# Boost.net
KiCad netlist of a schematic drawn in Altium Designer
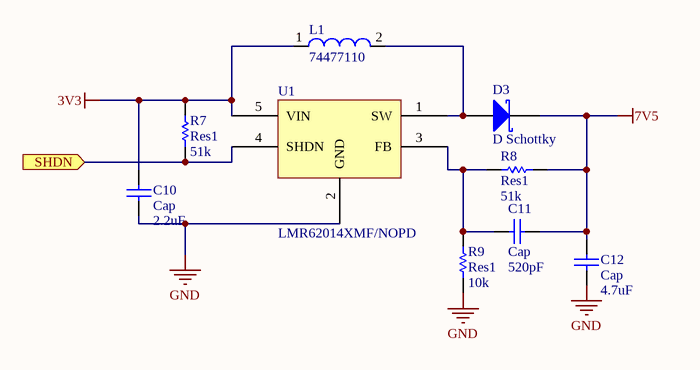
[diagram p0: Boost.SchDoc]

(export (version "E")
  (design (tool "Eeschema 10.0.6"))
  (components
    (comp (ref "C10")
      (value "Cap")
      (footprint "1608[0603]")
      (description "Capacitor")
      (fields (field (name "ALTIUM_VALUE") "2.2uF") (field (name "PUBLISHER") "Altium Limited"))
      (libsource (lib "Miscellaneous Devices") (part "Cap"))
    )
    (comp (ref "C11")
      (value "Cap")
      (footprint "6-0805_N")
      (description "Capacitor")
      (fields (field (name "ALTIUM_VALUE") "520pF") (field (name "PUBLISHER") "Altium Limited"))
      (libsource (lib "Miscellaneous Devices") (part "Cap"))
    )
    (comp (ref "C12")
      (value "Cap")
      (footprint "6-0805_N")
      (description "Capacitor")
      (fields (field (name "ALTIUM_VALUE") "4.7uF") (field (name "PUBLISHER") "Altium Limited"))
      (libsource (lib "Miscellaneous Devices") (part "Cap"))
    )
    (comp (ref "D3")
      (value "D Schottky")
      (footprint "CDBA5")
      (description "Schottky Diode")
      (fields (field (name "PUBLISHER") "Altium Limited"))
      (libsource (lib "Miscellaneous Devices") (part "D Schottky"))
    )
    (comp (ref "L1")
      (value "74477110")
      (footprint "WE-PD-L")
      (description "SMD-Shielded Power Inductor WE-PD, L = 10.0 µH")
      (libsource (lib "Altium Content Vault") (part "PAS-IND-INDUCTOR-2"))
    )
    (comp (ref "R7")
      (value "Res1")
      (footprint "1608[0603]")
      (description "Resistor")
      (fields (field (name "ALTIUM_VALUE") "51k") (field (name "PUBLISHER") "Altium Limited"))
      (libsource (lib "Miscellaneous Devices") (part "Res1"))
    )
    (comp (ref "R8")
      (value "Res1")
      (footprint "1608[0603]")
      (description "Resistor")
      (fields (field (name "ALTIUM_VALUE") "51k") (field (name "PUBLISHER") "Altium Limited"))
      (libsource (lib "Miscellaneous Devices") (part "Res1"))
    )
    (comp (ref "R9")
      (value "Res1")
      (footprint "0402-A")
      (description "Resistor")
      (fields (field (name "ALTIUM_VALUE") "10k") (field (name "PUBLISHER") "Altium Limited"))
      (libsource (lib "Miscellaneous Devices") (part "Res1"))
    )
    (comp (ref "U1")
      (value "LMR62014XMF/NOPD")
      (footprint "SOT95P280X145-5N")
      (libsource (lib "BPDC Library") (part "LMR62014XMF/NOPD"))
    )
  )
  (nets
    (net (code "1") (name "/SHDN") (class "Default")
      (node (ref "R7") (pin "2") (pinfunction "2_2") (pintype "passive"))
      (node (ref "U1") (pin "4") (pinfunction "SHDN_4") (pintype "passive"))
    )
    (net (code "2") (name "3V3") (class "Default")
      (node (ref "C10") (pin "2") (pinfunction "2_2") (pintype "passive"))
      (node (ref "L1") (pin "1") (pinfunction "1_1") (pintype "passive"))
      (node (ref "R7") (pin "1") (pinfunction "1_1") (pintype "passive"))
      (node (ref "U1") (pin "5") (pinfunction "VIN_5") (pintype "passive"))
    )
    (net (code "3") (name "7V5") (class "Default")
      (node (ref "C11") (pin "1") (pinfunction "1_1") (pintype "passive"))
      (node (ref "C12") (pin "2") (pinfunction "2_2") (pintype "passive"))
      (node (ref "D3") (pin "2") (pinfunction "K_2") (pintype "passive"))
      (node (ref "R8") (pin "2") (pinfunction "2_2") (pintype "passive"))
    )
    (net (code "4") (name "GND") (class "Default")
      (node (ref "C10") (pin "1") (pinfunction "1_1") (pintype "passive"))
      (node (ref "C12") (pin "1") (pinfunction "1_1") (pintype "passive"))
      (node (ref "R9") (pin "2") (pinfunction "2_2") (pintype "passive"))
      (node (ref "U1") (pin "2") (pinfunction "GND_2") (pintype "passive"))
    )
    (net (code "5") (name "Net-(D3-A)") (class "Default")
      (node (ref "D3") (pin "1") (pinfunction "A_1") (pintype "passive"))
      (node (ref "L1") (pin "2") (pinfunction "2_2") (pintype "passive"))
      (node (ref "U1") (pin "1") (pinfunction "SW_1") (pintype "passive"))
    )
    (net (code "6") (name "Net-(U1-FB)") (class "Default")
      (node (ref "C11") (pin "2") (pinfunction "2_2") (pintype "passive"))
      (node (ref "R8") (pin "1") (pinfunction "1_1") (pintype "passive"))
      (node (ref "R9") (pin "1") (pinfunction "1_1") (pintype "passive"))
      (node (ref "U1") (pin "3") (pinfunction "FB_3") (pintype "passive"))
    )
  )
)
